# projet_pcb_etu_formatA3.net
KiCad netlist of a schematic drawn in Altium Designer
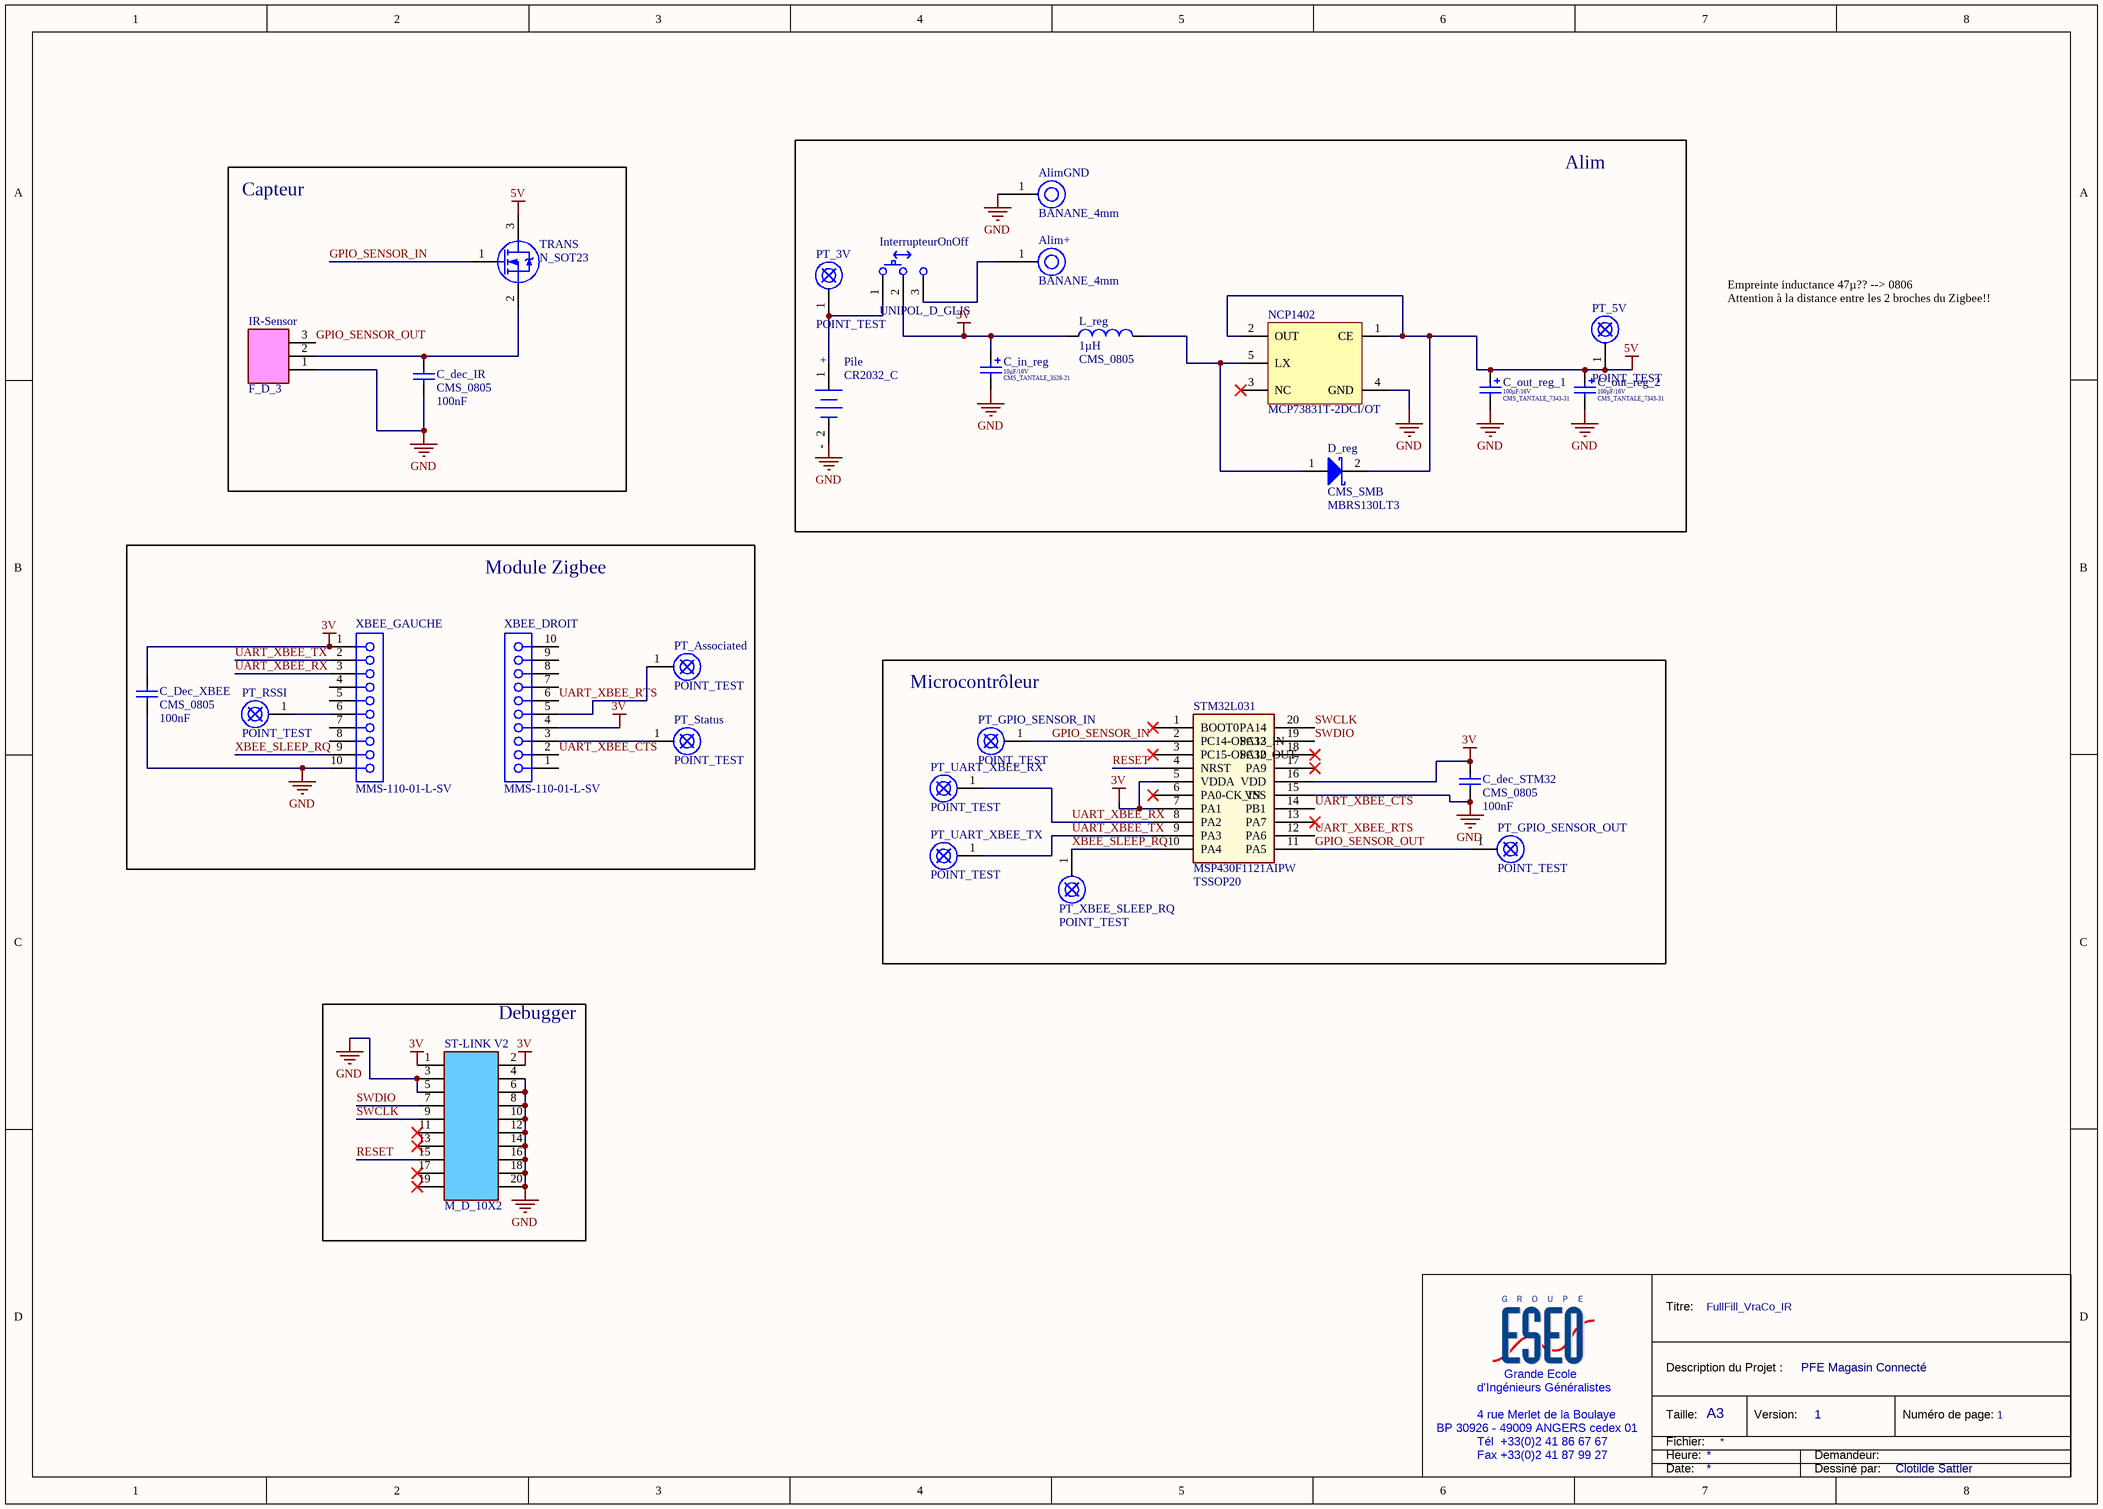
[diagram p0: projet_pcb_etu_formatA3.SchDoc]

(export (version "E")
  (design (tool "Eeschema 10.0.6"))
  (components
    (comp (ref "Alim+")
      (value "DOUILLE BANANE 4mm")
      (footprint "DOUILLE_BANANE_4mm")
      (description "DOUILLE BANANE 4 mm")
      (fields (field (name "TYPE") "BANANE_4mm"))
      (libsource (lib "connecteurs") (part "DOUILLE_BANANE_4mm"))
    )
    (comp (ref "AlimGND")
      (value "DOUILLE BANANE 4mm")
      (footprint "DOUILLE_BANANE_4mm")
      (description "DOUILLE BANANE 4 mm")
      (fields (field (name "TYPE") "BANANE_4mm"))
      (libsource (lib "connecteurs") (part "DOUILLE_BANANE_4mm"))
    )
    (comp (ref "C_dec_IR")
      (value "100nF")
      (footprint "CONDENSATEUR_CMS_0805")
      (description "CONDENSATEUR CMS CERAMIQUE 0805")
      (fields (field (name "TYPE") "CMS_0805") (field (name "Comment") "CMS_0805"))
      (libsource (lib "composants passifs") (part "CONDENSATEUR_CMS_CER_0805"))
    )
    (comp (ref "C_dec_STM32")
      (value "100nF")
      (footprint "CONDENSATEUR_CMS_0805")
      (description "CONDENSATEUR CMS CERAMIQUE 0805")
      (fields (field (name "TYPE") "CMS_0805") (field (name "Comment") "CMS_0805"))
      (libsource (lib "composants passifs") (part "CONDENSATEUR_CMS_CER_0805"))
    )
    (comp (ref "C_Dec_XBEE")
      (value "100nF")
      (footprint "CONDENSATEUR_CMS_0805")
      (description "CONDENSATEUR CMS CERAMIQUE 0805")
      (fields (field (name "TYPE") "CMS_0805") (field (name "Comment") "CMS_0805"))
      (libsource (lib "composants passifs") (part "CONDENSATEUR_CMS_CER_0805"))
    )
    (comp (ref "C_in_reg")
      (value "10µF/16V")
      (footprint "CONDENSATEUR_CMS_POLARISE_TANTALE_B/3528-21")
      (description "CONDENSATEUR CMS POLARISE TANTALE BOITIER B/3528-21")
      (fields
        (field (name "TYPE") "CMS_TANTALE_3528-21")
        (field (name "Comment") "CMS_POLARISE_TANTALE_3528-21")
      )
      (libsource (lib "composants passifs") (part "CONDENSATEUR_CMS_POL_TANT_B_3528-21"))
    )
    (comp (ref "C_out_reg_1")
      (value "100µF/16V")
      (footprint "CONDENSATEUR_CMS_POLARISE_TANTALE_D/7343-31")
      (description "CONDENSATEUR CMS POLARISE TANTALE BOITIER D/7343-31")
      (fields
        (field (name "TYPE") "CMS_TANTALE_7343-31")
        (field (name "Comment") "CMS_POLARISE_TANTALE_7343-31")
      )
      (libsource (lib "composants passifs") (part "CONDENSATEUR_CMS_POL_TANT_D_7343-31"))
    )
    (comp (ref "C_out_reg_2")
      (value "100µF/16V")
      (footprint "CONDENSATEUR_CMS_POLARISE_TANTALE_D/7343-31")
      (description "CONDENSATEUR CMS POLARISE TANTALE BOITIER D/7343-31")
      (fields
        (field (name "TYPE") "CMS_TANTALE_7343-31")
        (field (name "Comment") "CMS_POLARISE_TANTALE_7343-31")
      )
      (libsource (lib "composants passifs") (part "CONDENSATEUR_CMS_POL_TANT_D_7343-31"))
    )
    (comp (ref "D_reg")
      (value "DIODE_CMS_SCHOTTKY_SMB : MBRS130LT3")
      (footprint "DIODE_CMS_SMB")
      (description "DIODE CMS SCHOTTKY SMB : MBRS130LT3")
      (fields (field (name "PACKAGE") "CMS_SMB") (field (name "TYPE") "MBRS130LT3"))
      (libsource (lib "composants actifs") (part "DIODE_CMS_SCHOTTKY_SMB {colon} MBRS130LT3"))
    )
    (comp (ref "InterrupteurOnOff")
      (value "INTERRUPTEUR_UNIPOLAIRE_DROIT_GLISSIERE")
      (footprint "INTER_UNIPOL_DROIT_GLISS")
      (description "INTERRUPTEUR UNIPOLAIRE DROIT A GLISSIERE")
      (fields (field (name "TYPE") "UNIPOL_D_GLIS"))
      (libsource (lib "commutation") (part "INTERRUPTEUR_UNIPOLAIRE_DROIT_GLISSIERE"))
    )
    (comp (ref "IR-Sensor")
      (value "BARRETTE 3 CONTACTS 1 RANGEE FEMELLE DROITE")
      (footprint "BARRETTE_3_F_D")
      (fields (field (name "TYPE") "F_D_3"))
      (libsource (lib "connecteurs") (part "BARRETTE_3 CONTACTS_1 RANGEE_FEMELLE_DROITE"))
    )
    (comp (ref "L_reg")
      (value "1µH")
      (footprint "INDUCTANCE_CMS_0805")
      (description "INDUCTANCE CMS 0805")
      (fields (field (name "TYPE") "CMS_0805") (field (name "Comment") "INDUCTANCE_CMS_0805"))
      (libsource (lib "composants passifs") (part "INDUCTANCE_CMS_0805"))
    )
    (comp (ref "NCP1402")
      (value "MCP73831T-2DCI/OT")
      (footprint "SOT-23-OT5_N")
      (fields (field (name "MANUFACTURER") "Microchip"))
      (libsource (lib "energie") (part "MCP73831T-2DCI/OT"))
    )
    (comp (ref "Pile")
      (value "PILE_CR2032_COUDEE")
      (footprint "PILE_CR2032_HORIZ")
      (description "PILE AU LITHIUM TYPE CR2032 COUDEE")
      (fields (field (name "TYPE") "CR2032_C"))
      (libsource (lib "energie") (part "PILE_LITHIUM_CR2032_COUDEE_1"))
    )
    (comp (ref "PT_3V")
      (value "POINT_TEST")
      (footprint "POINT_TEST")
      (description "POINT TEST")
      (libsource (lib "connecteurs") (part "POINT_TEST"))
    )
    (comp (ref "PT_5V")
      (value "POINT_TEST")
      (footprint "POINT_TEST")
      (description "POINT TEST")
      (libsource (lib "connecteurs") (part "POINT_TEST"))
    )
    (comp (ref "PT_Associated")
      (value "POINT_TEST")
      (footprint "POINT_TEST")
      (description "POINT TEST")
      (libsource (lib "connecteurs") (part "POINT_TEST"))
    )
    (comp (ref "PT_GPIO_SENSOR_IN")
      (value "POINT_TEST")
      (footprint "POINT_TEST")
      (description "POINT TEST")
      (libsource (lib "connecteurs") (part "POINT_TEST"))
    )
    (comp (ref "PT_GPIO_SENSOR_OUT")
      (value "POINT_TEST")
      (footprint "POINT_TEST")
      (description "POINT TEST")
      (libsource (lib "connecteurs") (part "POINT_TEST"))
    )
    (comp (ref "PT_RSSI")
      (value "POINT_TEST")
      (footprint "POINT_TEST")
      (description "POINT TEST")
      (libsource (lib "connecteurs") (part "POINT_TEST"))
    )
    (comp (ref "PT_Status")
      (value "POINT_TEST")
      (footprint "POINT_TEST")
      (description "POINT TEST")
      (libsource (lib "connecteurs") (part "POINT_TEST"))
    )
    (comp (ref "PT_UART_XBEE_RX")
      (value "POINT_TEST")
      (footprint "POINT_TEST")
      (description "POINT TEST")
      (libsource (lib "connecteurs") (part "POINT_TEST"))
    )
    (comp (ref "PT_UART_XBEE_TX")
      (value "POINT_TEST")
      (footprint "POINT_TEST")
      (description "POINT TEST")
      (libsource (lib "connecteurs") (part "POINT_TEST"))
    )
    (comp (ref "PT_XBEE_SLEEP_RQ")
      (value "POINT_TEST")
      (footprint "POINT_TEST")
      (description "POINT TEST")
      (libsource (lib "connecteurs") (part "POINT_TEST"))
    )
    (comp (ref "ST-LINK V2")
      (value "BARRETTE_10 CONTACTS_2 RANGEES_MALE_DROITE")
      (footprint "BARRETTE_10X2_M_D")
      (fields (field (name "TYPE") "M_D_10X2"))
      (libsource (lib "connecteurs") (part "BARRETTE_10 CONTACTS_2 RANGEES_MALE_DROITE"))
    )
    (comp (ref "STM32L031")
      (value "MSP430F1121AIPW_TSSOP20")
      (footprint "TSSOP20_PAS=0.65_LARG=6.4_LONG=6.5")
      (description "MICROCONTROLEUR FLASH - 16BITS - TSSOP20")
      (fields (field (name "TYPE") "MSP430F1121AIPW") (field (name "PACKAGE") "TSSOP20"))
      (libsource (lib "circuits integres") (part "MSP430F1121AIPW_TSSOP20"))
    )
    (comp (ref "TRANS")
      (value "TRANSISTOR_MOSFET-N_SOT23_GSD")
      (footprint "TRANSISTOR_MOSFET-N_SOT23_GSD")
      (description "TRANSISTOR MOSFET CANAL N BOITIER SOT23_GSD")
      (fields (field (name "PACKAGE") "N_SOT23"))
      (libsource (lib "composants actifs") (part "TRANSISTOR_MOSFET-N_SOT23_GSD"))
    )
    (comp (ref "XBEE_DROIT")
      (value "MMS-110-01-L-SV")
      (footprint "SMTC-MMS-110-01-X-SV")
      (fields (field (name "MANUFACTURER") "Samtec"))
      (libsource (lib "Samtec_2_mm_Pitch_Socket_Strips") (part "MMS-110-01-L-SV"))
    )
    (comp (ref "XBEE_GAUCHE")
      (value "MMS-110-01-L-SV")
      (footprint "SMTC-MMS-110-01-X-SV")
      (fields (field (name "MANUFACTURER") "Samtec"))
      (libsource (lib "Samtec_2_mm_Pitch_Socket_Strips") (part "MMS-110-01-L-SV"))
    )
  )
  (nets
    (net (code "1") (name "/GPIO_SENSOR_IN") (class "Default")
      (node (ref "PT_GPIO_SENSOR_IN") (pin "1") (pinfunction "3_1") (pintype "passive"))
      (node (ref "STM32L031") (pin "2") (pinfunction "PC14-OSC32_IN_2") (pintype "passive"))
      (node (ref "TRANS") (pin "1") (pinfunction "G_1") (pintype "passive"))
    )
    (net (code "2") (name "/GPIO_SENSOR_OUT") (class "Default")
      (node (ref "IR-Sensor") (pin "3") (pinfunction "OUT_3") (pintype "passive"))
      (node (ref "PT_GPIO_SENSOR_OUT") (pin "1") (pinfunction "3_1") (pintype "passive"))
      (node (ref "STM32L031") (pin "11") (pinfunction "PA5_11") (pintype "passive"))
    )
    (net (code "3") (name "/RESET") (class "Default")
      (node (ref "ST-LINK V2") (pin "15") (pinfunction "15_15") (pintype "passive"))
      (node (ref "STM32L031") (pin "4") (pinfunction "NRST_4") (pintype "passive"))
    )
    (net (code "4") (name "/SWCLK") (class "Default")
      (node (ref "ST-LINK V2") (pin "9") (pinfunction "9_9") (pintype "passive"))
      (node (ref "STM32L031") (pin "20") (pinfunction "PA14_20") (pintype "passive"))
    )
    (net (code "5") (name "/SWDIO") (class "Default")
      (node (ref "ST-LINK V2") (pin "7") (pinfunction "7_7") (pintype "passive"))
      (node (ref "STM32L031") (pin "19") (pinfunction "PA13_19") (pintype "passive"))
    )
    (net (code "6") (name "/UART_XBEE_CTS") (class "Default")
      (node (ref "STM32L031") (pin "14") (pinfunction "PB1_14") (pintype "passive"))
      (node (ref "XBEE_DROIT") (pin "2") (pinfunction "12_2") (pintype "passive"))
    )
    (net (code "7") (name "/UART_XBEE_RTS") (class "Default")
      (node (ref "STM32L031") (pin "12") (pinfunction "PA6_12") (pintype "passive"))
      (node (ref "XBEE_DROIT") (pin "6") (pinfunction "16_6") (pintype "passive"))
    )
    (net (code "8") (name "/UART_XBEE_RX") (class "Default")
      (node (ref "PT_UART_XBEE_RX") (pin "1") (pinfunction "3_1") (pintype "passive"))
      (node (ref "STM32L031") (pin "8") (pinfunction "PA2_8") (pintype "passive"))
      (node (ref "XBEE_GAUCHE") (pin "3") (pinfunction "13_3") (pintype "passive"))
    )
    (net (code "9") (name "/UART_XBEE_TX") (class "Default")
      (node (ref "PT_UART_XBEE_TX") (pin "1") (pinfunction "3_1") (pintype "passive"))
      (node (ref "STM32L031") (pin "9") (pinfunction "PA3_9") (pintype "passive"))
      (node (ref "XBEE_GAUCHE") (pin "2") (pinfunction "12_2") (pintype "passive"))
    )
    (net (code "10") (name "/XBEE_SLEEP_RQ") (class "Default")
      (node (ref "PT_XBEE_SLEEP_RQ") (pin "1") (pinfunction "3_1") (pintype "passive"))
      (node (ref "STM32L031") (pin "10") (pinfunction "PA4_10") (pintype "passive"))
      (node (ref "XBEE_GAUCHE") (pin "9") (pinfunction "19_9") (pintype "passive"))
    )
    (net (code "11") (name "3V") (class "Default")
      (node (ref "C_Dec_XBEE") (pin "2") (pinfunction "2_2") (pintype "passive"))
      (node (ref "C_dec_STM32") (pin "2") (pinfunction "2_2") (pintype "passive"))
      (node (ref "C_in_reg") (pin "1") (pinfunction "1_1") (pintype "passive"))
      (node (ref "InterrupteurOnOff") (pin "2") (pinfunction "2_2") (pintype "passive"))
      (node (ref "L_reg") (pin "1") (pinfunction "1_1") (pintype "passive"))
      (node (ref "ST-LINK V2") (pin "1") (pinfunction "1_1") (pintype "passive"))
      (node (ref "ST-LINK V2") (pin "2") (pinfunction "2_2") (pintype "passive"))
      (node (ref "STM32L031") (pin "16") (pinfunction "VDD_16") (pintype "passive"))
      (node (ref "STM32L031") (pin "5") (pinfunction "VDDA_5") (pintype "passive"))
      (node (ref "STM32L031") (pin "7") (pinfunction "PA1_7") (pintype "passive"))
      (node (ref "XBEE_DROIT") (pin "4") (pinfunction "14_4") (pintype "passive"))
      (node (ref "XBEE_GAUCHE") (pin "1") (pinfunction "11_1") (pintype "passive"))
    )
    (net (code "12") (name "5V") (class "Default")
      (node (ref "C_out_reg_1") (pin "1") (pinfunction "1_1") (pintype "passive"))
      (node (ref "C_out_reg_2") (pin "1") (pinfunction "1_1") (pintype "passive"))
      (node (ref "D_reg") (pin "2") (pinfunction "2_2") (pintype "passive"))
      (node (ref "NCP1402") (pin "1") (pinfunction "CE_1") (pintype "passive"))
      (node (ref "NCP1402") (pin "2") (pinfunction "OUT_2") (pintype "passive"))
      (node (ref "PT_5V") (pin "1") (pinfunction "3_1") (pintype "passive"))
      (node (ref "TRANS") (pin "3") (pinfunction "D_3") (pintype "passive"))
    )
    (net (code "13") (name "GND") (class "Default")
      (node (ref "AlimGND") (pin "1") (pinfunction "1_1") (pintype "passive"))
      (node (ref "C_Dec_XBEE") (pin "1") (pinfunction "1_1") (pintype "passive"))
      (node (ref "C_dec_IR") (pin "1") (pinfunction "1_1") (pintype "passive"))
      (node (ref "C_dec_STM32") (pin "1") (pinfunction "1_1") (pintype "passive"))
      (node (ref "C_in_reg") (pin "2") (pinfunction "2_2") (pintype "passive"))
      (node (ref "C_out_reg_1") (pin "2") (pinfunction "2_2") (pintype "passive"))
      (node (ref "C_out_reg_2") (pin "2") (pinfunction "2_2") (pintype "passive"))
      (node (ref "IR-Sensor") (pin "1") (pinfunction "GND_1") (pintype "passive"))
      (node (ref "NCP1402") (pin "4") (pinfunction "GND_4") (pintype "power_in"))
      (node (ref "Pile") (pin "2") (pinfunction "-_2") (pintype "passive"))
      (node (ref "ST-LINK V2") (pin "10") (pinfunction "10_10") (pintype "passive"))
      (node (ref "ST-LINK V2") (pin "12") (pinfunction "12_12") (pintype "passive"))
      (node (ref "ST-LINK V2") (pin "14") (pinfunction "14_14") (pintype "passive"))
      (node (ref "ST-LINK V2") (pin "16") (pinfunction "16_16") (pintype "passive"))
      (node (ref "ST-LINK V2") (pin "18") (pinfunction "18_18") (pintype "passive"))
      (node (ref "ST-LINK V2") (pin "20") (pinfunction "20_20") (pintype "passive"))
      (node (ref "ST-LINK V2") (pin "3") (pinfunction "3_3") (pintype "passive"))
      (node (ref "ST-LINK V2") (pin "4") (pinfunction "4_4") (pintype "passive"))
      (node (ref "ST-LINK V2") (pin "5") (pinfunction "5_5") (pintype "passive"))
      (node (ref "ST-LINK V2") (pin "6") (pinfunction "6_6") (pintype "passive"))
      (node (ref "ST-LINK V2") (pin "8") (pinfunction "8_8") (pintype "passive"))
      (node (ref "STM32L031") (pin "15") (pinfunction "VSS_15") (pintype "passive"))
      (node (ref "XBEE_GAUCHE") (pin "10") (pinfunction "20_10") (pintype "passive"))
    )
    (net (code "14") (name "Net-(Alim+-Pad1)") (class "Default")
      (node (ref "Alim+") (pin "1") (pinfunction "1_1") (pintype "passive"))
      (node (ref "InterrupteurOnOff") (pin "3") (pinfunction "3_3") (pintype "passive"))
    )
    (net (code "15") (name "Net-(IR-Sensor-VCC)") (class "Default")
      (node (ref "C_dec_IR") (pin "2") (pinfunction "2_2") (pintype "passive"))
      (node (ref "IR-Sensor") (pin "2") (pinfunction "VCC_2") (pintype "passive"))
      (node (ref "TRANS") (pin "2") (pinfunction "S_2") (pintype "passive"))
    )
    (net (code "16") (name "Net-(NCP1402-LX)") (class "Default")
      (node (ref "D_reg") (pin "1") (pinfunction "1_1") (pintype "passive"))
      (node (ref "L_reg") (pin "2") (pinfunction "2_2") (pintype "passive"))
      (node (ref "NCP1402") (pin "5") (pinfunction "LX_5") (pintype "passive"))
    )
    (net (code "17") (name "Net-(PT_3V-3)") (class "Default")
      (node (ref "InterrupteurOnOff") (pin "1") (pinfunction "1_1") (pintype "passive"))
      (node (ref "PT_3V") (pin "1") (pinfunction "3_1") (pintype "passive"))
      (node (ref "Pile") (pin "1") (pinfunction "+_1") (pintype "passive"))
    )
    (net (code "18") (name "Net-(PT_Associated-3)") (class "Default")
      (node (ref "PT_Associated") (pin "1") (pinfunction "3_1") (pintype "passive"))
      (node (ref "XBEE_DROIT") (pin "5") (pinfunction "15_5") (pintype "passive"))
    )
    (net (code "19") (name "Net-(PT_RSSI-3)") (class "Default")
      (node (ref "PT_RSSI") (pin "1") (pinfunction "3_1") (pintype "passive"))
      (node (ref "XBEE_GAUCHE") (pin "6") (pinfunction "16_6") (pintype "passive"))
    )
    (net (code "20") (name "Net-(PT_Status-3)") (class "Default")
      (node (ref "PT_Status") (pin "1") (pinfunction "3_1") (pintype "passive"))
      (node (ref "XBEE_DROIT") (pin "3") (pinfunction "13_3") (pintype "passive"))
    )
    (net (code "21") (name "unconnected-(NCP1402-NC-Pad3)") (class "Default")
      (node (ref "NCP1402") (pin "3") (pinfunction "NC_3") (pintype "passive+no_connect"))
    )
    (net (code "22") (name "unconnected-(ST-LINK V2-Pad11)") (class "Default")
      (node (ref "ST-LINK V2") (pin "11") (pinfunction "11_11") (pintype "passive+no_connect"))
    )
    (net (code "23") (name "unconnected-(ST-LINK V2-Pad13)") (class "Default")
      (node (ref "ST-LINK V2") (pin "13") (pinfunction "13_13") (pintype "passive+no_connect"))
    )
    (net (code "24") (name "unconnected-(ST-LINK V2-Pad17)") (class "Default")
      (node (ref "ST-LINK V2") (pin "17") (pinfunction "17_17") (pintype "passive+no_connect"))
    )
    (net (code "25") (name "unconnected-(ST-LINK V2-Pad19)") (class "Default")
      (node (ref "ST-LINK V2") (pin "19") (pinfunction "19_19") (pintype "passive+no_connect"))
    )
    (net (code "26") (name "unconnected-(STM32L031-BOOT0-Pad1)") (class "Default")
      (node (ref "STM32L031") (pin "1") (pinfunction "BOOT0_1") (pintype "passive+no_connect"))
    )
    (net (code "27") (name "unconnected-(STM32L031-PA0-CK_IN-Pad6)") (class "Default")
      (node (ref "STM32L031") (pin "6") (pinfunction "PA0-CK_IN_6") (pintype "passive+no_connect"))
    )
    (net (code "28") (name "unconnected-(STM32L031-PA7-Pad13)") (class "Default")
      (node (ref "STM32L031") (pin "13") (pinfunction "PA7_13") (pintype "passive+no_connect"))
    )
    (net (code "29") (name "unconnected-(STM32L031-PA9-Pad17)") (class "Default")
      (node (ref "STM32L031") (pin "17") (pinfunction "PA9_17") (pintype "passive+no_connect"))
    )
    (net (code "30") (name "unconnected-(STM32L031-PA10-Pad18)") (class "Default")
      (node (ref "STM32L031") (pin "18") (pinfunction "PA10_18") (pintype "passive+no_connect"))
    )
    (net (code "31") (name "unconnected-(STM32L031-PC15-OSC32_OUT-Pad3)") (class "Default")
      (node (ref "STM32L031") (pin "3") (pinfunction "PC15-OSC32_OUT_3") (pintype "passive+no_connect"))
    )
    (net (code "32") (name "unconnected-(XBEE_DROIT-11-Pad1)") (class "Default")
      (node (ref "XBEE_DROIT") (pin "1") (pinfunction "11_1") (pintype "passive"))
    )
    (net (code "33") (name "unconnected-(XBEE_DROIT-17-Pad7)") (class "Default")
      (node (ref "XBEE_DROIT") (pin "7") (pinfunction "17_7") (pintype "passive"))
    )
    (net (code "34") (name "unconnected-(XBEE_DROIT-18-Pad8)") (class "Default")
      (node (ref "XBEE_DROIT") (pin "8") (pinfunction "18_8") (pintype "passive"))
    )
    (net (code "35") (name "unconnected-(XBEE_DROIT-19-Pad9)") (class "Default")
      (node (ref "XBEE_DROIT") (pin "9") (pinfunction "19_9") (pintype "passive"))
    )
    (net (code "36") (name "unconnected-(XBEE_DROIT-20-Pad10)") (class "Default")
      (node (ref "XBEE_DROIT") (pin "10") (pinfunction "20_10") (pintype "passive"))
    )
    (net (code "37") (name "unconnected-(XBEE_GAUCHE-14-Pad4)") (class "Default")
      (node (ref "XBEE_GAUCHE") (pin "4") (pinfunction "14_4") (pintype "passive"))
    )
    (net (code "38") (name "unconnected-(XBEE_GAUCHE-15-Pad5)") (class "Default")
      (node (ref "XBEE_GAUCHE") (pin "5") (pinfunction "15_5") (pintype "passive"))
    )
    (net (code "39") (name "unconnected-(XBEE_GAUCHE-17-Pad7)") (class "Default")
      (node (ref "XBEE_GAUCHE") (pin "7") (pinfunction "17_7") (pintype "passive"))
    )
    (net (code "40") (name "unconnected-(XBEE_GAUCHE-18-Pad8)") (class "Default")
      (node (ref "XBEE_GAUCHE") (pin "8") (pinfunction "18_8") (pintype "passive"))
    )
  )
)
